# l293d_module.net
KiCad netlist of a schematic drawn in EAGLE
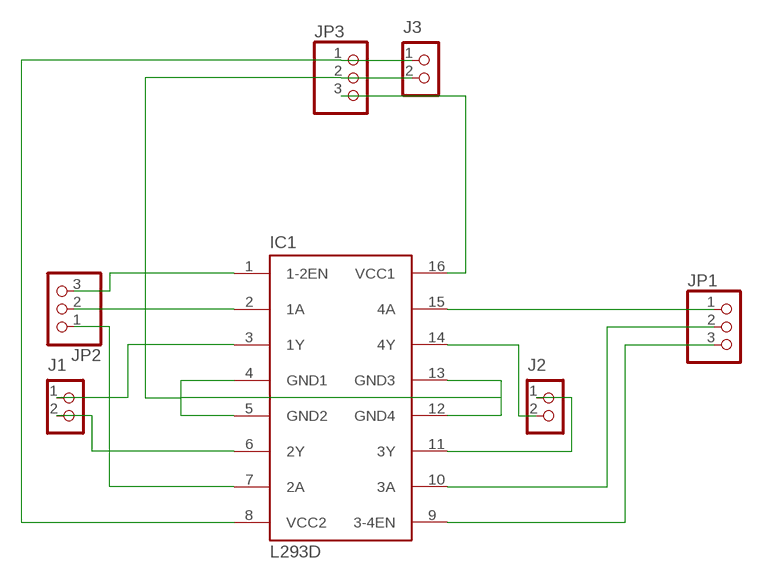
[diagram p0: schematic, sheet 1]

(export (version "E")
  (design (tool "Eeschema 10.0.6"))
  (components
    (comp (ref "IC1")
      (value "L293D")
      (footprint "eagle-import:DIL16")
      (libsource (lib "eagle-import") (part "L293D"))
    )
    (comp (ref "J1")
      (value "CON_TERMINAL_BLOCK_02-5MM")
      (footprint "eagle-import:TERMINAL_BLOCK_2P_5")
      (libsource (lib "eagle-import") (part "CON_TERMINAL_BLOCK_02-5MM"))
    )
    (comp (ref "J2")
      (value "CON_TERMINAL_BLOCK_02-5MM")
      (footprint "eagle-import:TERMINAL_BLOCK_2P_5")
      (libsource (lib "eagle-import") (part "CON_TERMINAL_BLOCK_02-5MM"))
    )
    (comp (ref "J3")
      (value "CON_TERMINAL_BLOCK_02-5MM")
      (footprint "eagle-import:TERMINAL_BLOCK_2P_5")
      (libsource (lib "eagle-import") (part "CON_TERMINAL_BLOCK_02-5MM"))
    )
    (comp (ref "JP1")
      (value "PINHD-1X3")
      (footprint "eagle-import:1X03")
      (libsource (lib "eagle-import") (part "PINHD-1X3"))
    )
    (comp (ref "JP2")
      (value "PINHD-1X3")
      (footprint "eagle-import:1X03")
      (libsource (lib "eagle-import") (part "PINHD-1X3"))
    )
    (comp (ref "JP3")
      (value "PINHD-1X3")
      (footprint "eagle-import:1X03")
      (libsource (lib "eagle-import") (part "PINHD-1X3"))
    )
  )
  (nets
    (net (code "1") (name "Net-(IC1-1-2EN)") (class "Default")
      (node (ref "IC1") (pin "1") (pinfunction "1-2EN_1") (pintype "input"))
      (node (ref "JP2") (pin "3") (pinfunction "3_3") (pintype "passive"))
    )
    (net (code "2") (name "Net-(IC1-1A)") (class "Default")
      (node (ref "IC1") (pin "2") (pinfunction "1A_2") (pintype "input"))
      (node (ref "JP2") (pin "2") (pinfunction "2_2") (pintype "passive"))
    )
    (net (code "3") (name "Net-(IC1-1Y)") (class "Default")
      (node (ref "IC1") (pin "3") (pinfunction "1Y_3") (pintype "output"))
      (node (ref "J1") (pin "1") (pinfunction "1_1") (pintype "passive"))
    )
    (net (code "4") (name "Net-(IC1-2A)") (class "Default")
      (node (ref "IC1") (pin "7") (pinfunction "2A_7") (pintype "input"))
      (node (ref "JP2") (pin "1") (pinfunction "1_1") (pintype "passive"))
    )
    (net (code "5") (name "Net-(IC1-2Y)") (class "Default")
      (node (ref "IC1") (pin "6") (pinfunction "2Y_6") (pintype "output"))
      (node (ref "J1") (pin "2") (pinfunction "2_2") (pintype "passive"))
    )
    (net (code "6") (name "Net-(IC1-3-4EN)") (class "Default")
      (node (ref "IC1") (pin "9") (pinfunction "3-4EN_9") (pintype "input"))
      (node (ref "JP1") (pin "3") (pinfunction "3_3") (pintype "passive"))
    )
    (net (code "7") (name "Net-(IC1-3A)") (class "Default")
      (node (ref "IC1") (pin "10") (pinfunction "3A_10") (pintype "input"))
      (node (ref "JP1") (pin "2") (pinfunction "2_2") (pintype "passive"))
    )
    (net (code "8") (name "Net-(IC1-3Y)") (class "Default")
      (node (ref "IC1") (pin "11") (pinfunction "3Y_11") (pintype "output"))
      (node (ref "J2") (pin "1") (pinfunction "1_1") (pintype "passive"))
    )
    (net (code "9") (name "Net-(IC1-4A)") (class "Default")
      (node (ref "IC1") (pin "15") (pinfunction "4A_15") (pintype "input"))
      (node (ref "JP1") (pin "1") (pinfunction "1_1") (pintype "passive"))
    )
    (net (code "10") (name "Net-(IC1-4Y)") (class "Default")
      (node (ref "IC1") (pin "14") (pinfunction "4Y_14") (pintype "output"))
      (node (ref "J2") (pin "2") (pinfunction "2_2") (pintype "passive"))
    )
    (net (code "11") (name "Net-(IC1-GND1)") (class "Default")
      (node (ref "IC1") (pin "12") (pinfunction "GND4_12") (pintype "power_in"))
      (node (ref "IC1") (pin "13") (pinfunction "GND3_13") (pintype "power_in"))
      (node (ref "IC1") (pin "4") (pinfunction "GND1_4") (pintype "power_in"))
      (node (ref "IC1") (pin "5") (pinfunction "GND2_5") (pintype "power_in"))
      (node (ref "J3") (pin "2") (pinfunction "2_2") (pintype "passive"))
      (node (ref "JP3") (pin "2") (pinfunction "2_2") (pintype "passive"))
    )
    (net (code "12") (name "Net-(IC1-VCC1)") (class "Default")
      (node (ref "IC1") (pin "16") (pinfunction "VCC1_16") (pintype "power_in"))
      (node (ref "JP3") (pin "3") (pinfunction "3_3") (pintype "passive"))
    )
    (net (code "13") (name "Net-(IC1-VCC2)") (class "Default")
      (node (ref "IC1") (pin "8") (pinfunction "VCC2_8") (pintype "power_in"))
      (node (ref "J3") (pin "1") (pinfunction "1_1") (pintype "passive"))
      (node (ref "JP3") (pin "1") (pinfunction "1_1") (pintype "passive"))
    )
  )
)
